# DS1338C_Breakout.net
KiCad netlist of a schematic drawn in EAGLE
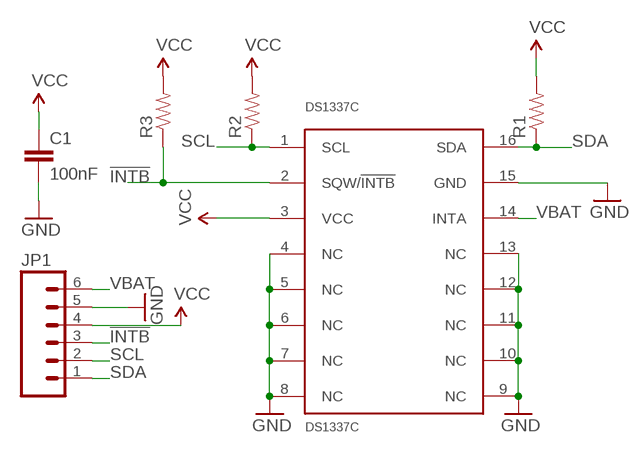
[diagram p0: schematic, sheet 1]

(export (version "E")
  (design (tool "Eeschema 10.0.6"))
  (components
    (comp (ref "C1")
      (value "100nF")
      (footprint "eagle-import:0603-CAP")
      (libsource (lib "eagle-import") (part "CAP0603-CAP"))
    )
    (comp (ref "DS1337C")
      (value "DS1337C")
      (footprint "eagle-import:DS1337C")
      (libsource (lib "eagle-import") (part "DS1337C"))
    )
    (comp (ref "JP1")
      (value "M06SIP")
      (footprint "eagle-import:1X06")
      (libsource (lib "eagle-import") (part "M06SIP"))
    )
    (comp (ref "R1")
      (value "RESISTOR0603-RES")
      (footprint "eagle-import:0603-RES")
      (libsource (lib "eagle-import") (part "RESISTOR0603-RES"))
    )
    (comp (ref "R2")
      (value "RESISTOR0603-RES")
      (footprint "eagle-import:0603-RES")
      (libsource (lib "eagle-import") (part "RESISTOR0603-RES"))
    )
    (comp (ref "R3")
      (value "RESISTOR0603-RES")
      (footprint "eagle-import:0603-RES")
      (libsource (lib "eagle-import") (part "RESISTOR0603-RES"))
    )
  )
  (nets
    (net (code "1") (name "/SCL") (class "Default")
      (node (ref "DS1337C") (pin "1") (pinfunction "SCL_1") (pintype "bidirectional"))
      (node (ref "JP1") (pin "2") (pinfunction "2_2") (pintype "passive"))
      (node (ref "R2") (pin "1") (pinfunction "1_1") (pintype "passive"))
    )
    (net (code "2") (name "/SDA") (class "Default")
      (node (ref "DS1337C") (pin "16") (pinfunction "SDA_16") (pintype "bidirectional"))
      (node (ref "JP1") (pin "1") (pinfunction "1_1") (pintype "passive"))
      (node (ref "R1") (pin "1") (pinfunction "1_1") (pintype "passive"))
    )
    (net (code "3") (name "/VBAT") (class "Default")
      (node (ref "DS1337C") (pin "14") (pinfunction "INTA_14") (pintype "bidirectional"))
      (node (ref "JP1") (pin "6") (pinfunction "6_6") (pintype "passive"))
    )
    (net (code "4") (name "/~{INTB}") (class "Default")
      (node (ref "DS1337C") (pin "2") (pinfunction "SQW/~{INTB}_2") (pintype "bidirectional"))
      (node (ref "JP1") (pin "3") (pinfunction "3_3") (pintype "passive"))
      (node (ref "R3") (pin "1") (pinfunction "1_1") (pintype "passive"))
    )
    (net (code "5") (name "GND") (class "Default")
      (node (ref "C1") (pin "2") (pinfunction "2_2") (pintype "passive"))
      (node (ref "DS1337C") (pin "10") (pinfunction "NC_10") (pintype "bidirectional"))
      (node (ref "DS1337C") (pin "11") (pinfunction "NC_11") (pintype "bidirectional"))
      (node (ref "DS1337C") (pin "12") (pinfunction "NC_12") (pintype "bidirectional"))
      (node (ref "DS1337C") (pin "13") (pinfunction "NC_13") (pintype "bidirectional"))
      (node (ref "DS1337C") (pin "15") (pinfunction "GND_15") (pintype "bidirectional"))
      (node (ref "DS1337C") (pin "4") (pinfunction "NC_4") (pintype "bidirectional"))
      (node (ref "DS1337C") (pin "5") (pinfunction "NC_5") (pintype "bidirectional"))
      (node (ref "DS1337C") (pin "6") (pinfunction "NC_6") (pintype "bidirectional"))
      (node (ref "DS1337C") (pin "7") (pinfunction "NC_7") (pintype "bidirectional"))
      (node (ref "DS1337C") (pin "8") (pinfunction "NC_8") (pintype "bidirectional"))
      (node (ref "DS1337C") (pin "9") (pinfunction "NC_9") (pintype "bidirectional"))
      (node (ref "JP1") (pin "5") (pinfunction "5_5") (pintype "passive"))
    )
    (net (code "6") (name "VCC") (class "Default")
      (node (ref "C1") (pin "1") (pinfunction "1_1") (pintype "passive"))
      (node (ref "DS1337C") (pin "3") (pinfunction "VCC_3") (pintype "bidirectional"))
      (node (ref "JP1") (pin "4") (pinfunction "4_4") (pintype "passive"))
      (node (ref "R1") (pin "2") (pinfunction "2_2") (pintype "passive"))
      (node (ref "R2") (pin "2") (pinfunction "2_2") (pintype "passive"))
      (node (ref "R3") (pin "2") (pinfunction "2_2") (pintype "passive"))
    )
  )
)
